# power.net
KiCad netlist of a schematic drawn in Altium Designer
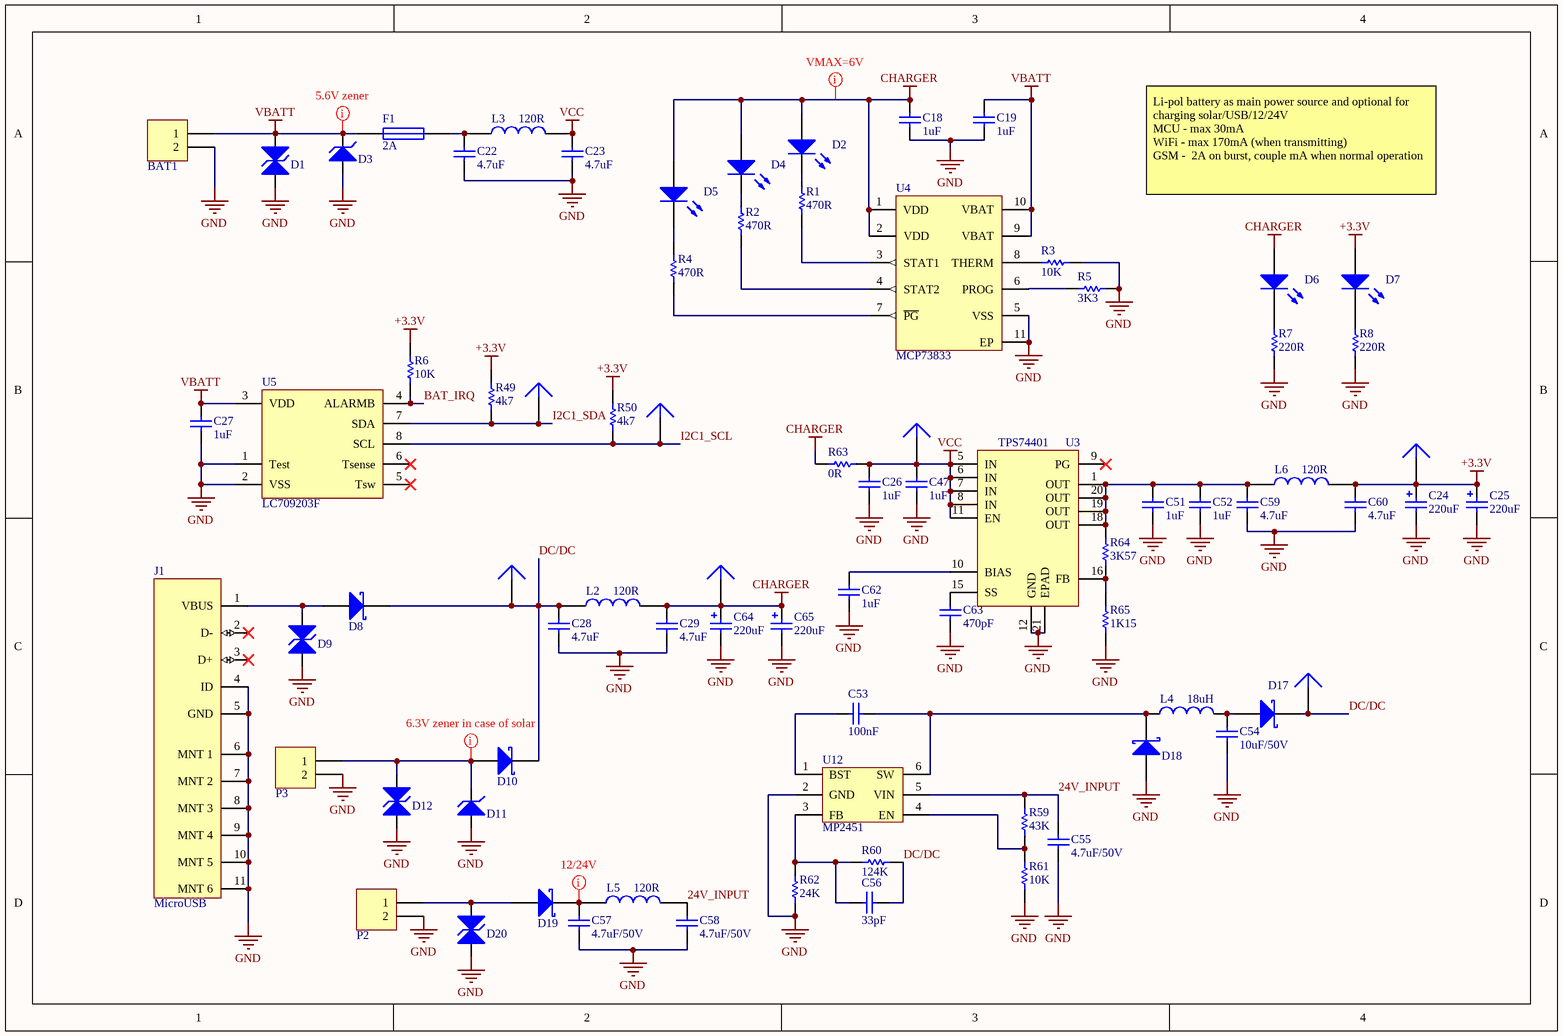
[diagram p0: power.SchDoc]

(export (version "E")
  (design (tool "Eeschema 10.0.6"))
  (components
    (comp (ref "BAT1")
      (value "Header 2")
      (footprint "HDR1X2")
      (description "Header, 2-Pin")
      (fields (field (name "PUBLISHER") "Altium Limited"))
      (libsource (lib "integratedLib") (part "Header 2"))
    )
    (comp (ref "C18")
      (value "1uF")
      (footprint "C0402")
      (description "Capacitor")
      (fields (field (name "Comment") "Cap 1uF"))
      (libsource (lib "integratedLib") (part "Cap 1uF"))
    )
    (comp (ref "C19")
      (value "1uF")
      (footprint "C0402")
      (description "Capacitor")
      (fields (field (name "Comment") "Cap 1uF"))
      (libsource (lib "integratedLib") (part "Cap 1uF"))
    )
    (comp (ref "C22")
      (value "4.7uF")
      (footprint "C0402")
      (description "Capacitor")
      (fields (field (name "Comment") "Cap 4.7uF"))
      (libsource (lib "integratedLib") (part "Cap 4.7uF"))
    )
    (comp (ref "C23")
      (value "4.7uF")
      (footprint "C0402")
      (description "Capacitor")
      (fields (field (name "Comment") "Cap 4.7uF"))
      (libsource (lib "integratedLib") (part "Cap 4.7uF"))
    )
    (comp (ref "C24")
      (value "220uF")
      (footprint "CAP-D")
      (description "Polarized Tantalum Capacitor")
      (fields (field (name "Comment") "Tantalum 220uF"))
      (libsource (lib "integratedLib") (part "Tantalum 220uF"))
    )
    (comp (ref "C25")
      (value "220uF")
      (footprint "CAP-D")
      (description "Polarized Tantalum Capacitor")
      (fields (field (name "Comment") "Tantalum 220uF"))
      (libsource (lib "integratedLib") (part "Tantalum 220uF"))
    )
    (comp (ref "C26")
      (value "1uF")
      (footprint "C0402")
      (description "Capacitor")
      (fields (field (name "Comment") "Cap 1uF"))
      (libsource (lib "integratedLib") (part "Cap 1uF"))
    )
    (comp (ref "C27")
      (value "1uF")
      (footprint "C0402")
      (description "Capacitor")
      (fields (field (name "Comment") "Cap 1uF"))
      (libsource (lib "integratedLib") (part "Cap 1uF"))
    )
    (comp (ref "C28")
      (value "4.7uF")
      (footprint "C0402")
      (description "Capacitor")
      (fields (field (name "Comment") "Cap 4.7uF"))
      (libsource (lib "integratedLib") (part "Cap 4.7uF"))
    )
    (comp (ref "C29")
      (value "4.7uF")
      (footprint "C0402")
      (description "Capacitor")
      (fields (field (name "Comment") "Cap 4.7uF"))
      (libsource (lib "integratedLib") (part "Cap 4.7uF"))
    )
    (comp (ref "C47")
      (value "1uF")
      (footprint "C0402")
      (description "Capacitor")
      (fields (field (name "Comment") "Cap 1uF"))
      (libsource (lib "integratedLib") (part "Cap 1uF"))
    )
    (comp (ref "C51")
      (value "1uF")
      (footprint "C0402")
      (description "Capacitor")
      (fields (field (name "Comment") "Cap 1uF"))
      (libsource (lib "integratedLib") (part "Cap 1uF"))
    )
    (comp (ref "C52")
      (value "1uF")
      (footprint "C0402")
      (description "Capacitor")
      (fields (field (name "Comment") "Cap 1uF"))
      (libsource (lib "integratedLib") (part "Cap 1uF"))
    )
    (comp (ref "C53")
      (value "100nF")
      (footprint "C0402")
      (description "Capacitor")
      (fields (field (name "Comment") "Cap 100nF"))
      (libsource (lib "integratedLib") (part "Cap 100nF"))
    )
    (comp (ref "C54")
      (value "10uF/50V")
      (footprint "C1206")
      (description "Capacitor")
      (fields (field (name "Comment") "Cap 10uF/50V"))
      (libsource (lib "integratedLib") (part "Cap 10uF/50V"))
    )
    (comp (ref "C55")
      (value "4.7uF/50V")
      (footprint "C1206")
      (description "Capacitor")
      (fields (field (name "Comment") "Cap 4.7uF/50V"))
      (libsource (lib "integratedLib") (part "Cap 4.7uF/50V"))
    )
    (comp (ref "C56")
      (value "33pF")
      (footprint "C0402")
      (description "Capacitor")
      (fields (field (name "Comment") "Cap 33pF"))
      (libsource (lib "integratedLib") (part "Cap 33pF"))
    )
    (comp (ref "C57")
      (value "4.7uF/50V")
      (footprint "C1206")
      (description "Capacitor")
      (fields (field (name "Comment") "Cap 4.7uF/50V"))
      (libsource (lib "integratedLib") (part "Cap 4.7uF/50V"))
    )
    (comp (ref "C58")
      (value "4.7uF/50V")
      (footprint "C1206")
      (description "Capacitor")
      (fields (field (name "Comment") "Cap 4.7uF/50V"))
      (libsource (lib "integratedLib") (part "Cap 4.7uF/50V"))
    )
    (comp (ref "C59")
      (value "4.7uF")
      (footprint "C0402")
      (description "Capacitor")
      (fields (field (name "Comment") "Cap 4.7uF"))
      (libsource (lib "integratedLib") (part "Cap 4.7uF"))
    )
    (comp (ref "C60")
      (value "4.7uF")
      (footprint "C0402")
      (description "Capacitor")
      (fields (field (name "Comment") "Cap 4.7uF"))
      (libsource (lib "integratedLib") (part "Cap 4.7uF"))
    )
    (comp (ref "C62")
      (value "1uF")
      (footprint "C0402")
      (description "Capacitor")
      (fields (field (name "Comment") "Cap 1uF"))
      (libsource (lib "integratedLib") (part "Cap 1uF"))
    )
    (comp (ref "C63")
      (value "470pF")
      (footprint "C0402")
      (description "Capacitor")
      (fields (field (name "Comment") "Cap 470pF"))
      (libsource (lib "integratedLib") (part "Cap 470pF"))
    )
    (comp (ref "C64")
      (value "220uF")
      (footprint "CAP-D")
      (description "Polarized Tantalum Capacitor")
      (fields (field (name "Comment") "Tantalum 220uF"))
      (libsource (lib "integratedLib") (part "Tantalum 220uF"))
    )
    (comp (ref "C65")
      (value "220uF")
      (footprint "CAP-D")
      (description "Polarized Tantalum Capacitor")
      (fields (field (name "Comment") "Tantalum 220uF"))
      (libsource (lib "integratedLib") (part "Tantalum 220uF"))
    )
    (comp (ref "D1")
      (value "TVS Bidirectional")
      (footprint "SMA")
      (description "SMAJ40CA")
      (fields (field (name "PUBLISHER") "Altium Limited"))
      (libsource (lib "integratedLib") (part "TVS_bidirectional"))
    )
    (comp (ref "D2")
      (value "LED")
      (footprint "0603LedRed")
      (description "Typical RED GaAs LED")
      (fields (field (name "PUBLISHER") "Altium Limited"))
      (libsource (lib "integratedLib") (part "LED"))
    )
    (comp (ref "D3")
      (value "Zener Diode")
      (footprint "miniMELF")
      (fields (field (name "PUBLISHER") "Altium Limited"))
      (libsource (lib "integratedLib") (part "Diode Zener"))
    )
    (comp (ref "D4")
      (value "LED")
      (footprint "0603LedRed")
      (description "Typical RED GaAs LED")
      (fields (field (name "PUBLISHER") "Altium Limited"))
      (libsource (lib "integratedLib") (part "LED"))
    )
    (comp (ref "D5")
      (value "LED")
      (footprint "0603LedRed")
      (description "Typical RED GaAs LED")
      (fields (field (name "PUBLISHER") "Altium Limited"))
      (libsource (lib "integratedLib") (part "LED"))
    )
    (comp (ref "D6")
      (value "LED")
      (footprint "0603LedRed")
      (description "Typical RED GaAs LED")
      (fields (field (name "PUBLISHER") "Altium Limited"))
      (libsource (lib "integratedLib") (part "LED"))
    )
    (comp (ref "D7")
      (value "LED")
      (footprint "0603LedRed")
      (description "Typical RED GaAs LED")
      (fields (field (name "PUBLISHER") "Altium Limited"))
      (libsource (lib "integratedLib") (part "LED"))
    )
    (comp (ref "D8")
      (value "STPS1L30U")
      (footprint "SOD-123A")
      (description "Schottky Rectifier")
      (fields (field (name "PUBLISHER") "Altium Limited"))
      (libsource (lib "integratedLib") (part "Diode Schottky"))
    )
    (comp (ref "D9")
      (value "TVS Bidirectional")
      (footprint "SMA")
      (description "SMAJ40CA")
      (fields (field (name "PUBLISHER") "Altium Limited"))
      (libsource (lib "integratedLib") (part "TVS_bidirectional"))
    )
    (comp (ref "D10")
      (value "STPS1L30U")
      (footprint "SOD-123A")
      (description "Schottky Rectifier")
      (fields (field (name "PUBLISHER") "Altium Limited"))
      (libsource (lib "integratedLib") (part "Diode Schottky"))
    )
    (comp (ref "D11")
      (value "Zener Diode")
      (footprint "miniMELF")
      (fields (field (name "PUBLISHER") "Altium Limited"))
      (libsource (lib "integratedLib") (part "Diode Zener"))
    )
    (comp (ref "D12")
      (value "TVS Bidirectional")
      (footprint "SMA")
      (description "SMAJ40CA")
      (fields (field (name "PUBLISHER") "Altium Limited"))
      (libsource (lib "integratedLib") (part "TVS_bidirectional"))
    )
    (comp (ref "D17")
      (value "D Schottky")
      (footprint "SOD-123A")
      (description "Schottky Diode")
      (fields (field (name "PUBLISHER") "Altium Limited"))
      (libsource (lib "supla_library") (part "D Schottky"))
    )
    (comp (ref "D18")
      (value "STPS1L30U")
      (footprint "SOD-123A")
      (description "Schottky Rectifier")
      (fields (field (name "PUBLISHER") "Altium Limited"))
      (libsource (lib "integratedLib") (part "Diode Schottky"))
    )
    (comp (ref "D19")
      (value "STPS1L30U")
      (footprint "SOD-123A")
      (description "Schottky Rectifier")
      (fields (field (name "PUBLISHER") "Altium Limited"))
      (libsource (lib "integratedLib") (part "Diode Schottky"))
    )
    (comp (ref "D20")
      (value "TVS Bidirectional")
      (footprint "SMA")
      (description "SMAJ40CA")
      (fields (field (name "PUBLISHER") "Altium Limited"))
      (libsource (lib "integratedLib") (part "TVS_bidirectional"))
    )
    (comp (ref "F1")
      (value "2A")
      (footprint "R1206")
      (description "Fuse\r\n2850030")
      (fields (field (name "PUBLISHER") "Altium Limited"))
      (libsource (lib "integratedLib") (part "Fuse_2A"))
    )
    (comp (ref "J1")
      (value "MicroUSB")
      (footprint "MicroUSB")
      (libsource (lib "integratedLib") (part "MicroUSB"))
    )
    (comp (ref "L2")
      (value "120R")
      (footprint "0805FerriteBead")
      (description "Ferrite bead")
      (fields (field (name "PUBLISHER") "Altium Limited"))
      (libsource (lib "integratedLib") (part "Ferrite bead 120R"))
    )
    (comp (ref "L3")
      (value "120R")
      (footprint "0805FerriteBead")
      (description "Ferrite bead")
      (fields (field (name "PUBLISHER") "Altium Limited"))
      (libsource (lib "integratedLib") (part "Ferrite bead 120R"))
    )
    (comp (ref "L4")
      (value "18uH")
      (footprint "WE-TPC_4828")
      (description "WE 744 043 180")
      (fields (field (name "Comment") "Inductor 18uH") (field (name "PUBLISHER") "Altium Limited"))
      (libsource (lib "integratedLib") (part "Inductor 18uH"))
    )
    (comp (ref "L5")
      (value "120R")
      (footprint "0805FerriteBead")
      (description "Ferrite bead")
      (fields (field (name "PUBLISHER") "Altium Limited"))
      (libsource (lib "integratedLib") (part "Ferrite bead 120R"))
    )
    (comp (ref "L6")
      (value "120R")
      (footprint "0805FerriteBead")
      (description "Ferrite bead")
      (fields (field (name "PUBLISHER") "Altium Limited"))
      (libsource (lib "integratedLib") (part "Ferrite bead 120R"))
    )
    (comp (ref "P2")
      (value "Header 2")
      (footprint "HDR1x2_screw")
      (description "Header, 2-Pin")
      (fields (field (name "PUBLISHER") "Altium Limited"))
      (libsource (lib "integratedLib") (part "Header 2"))
    )
    (comp (ref "P3")
      (value "Header 2")
      (footprint "HDR1x2_screw")
      (description "Header, 2-Pin")
      (fields (field (name "PUBLISHER") "Altium Limited"))
      (libsource (lib "integratedLib") (part "Header 2"))
    )
    (comp (ref "P12")
      (value "Plug")
      (footprint "pin smd")
      (fields (field (name "PUBLISHER") "Altium Limited"))
      (libsource (lib "integratedLib") (part "Plug"))
    )
    (comp (ref "P13")
      (value "Plug")
      (footprint "pin smd")
      (fields (field (name "PUBLISHER") "Altium Limited"))
      (libsource (lib "integratedLib") (part "Plug"))
    )
    (comp (ref "P15")
      (value "Plug")
      (footprint "pin smd")
      (fields (field (name "PUBLISHER") "Altium Limited"))
      (libsource (lib "integratedLib") (part "Plug"))
    )
    (comp (ref "P16")
      (value "Plug")
      (footprint "pin smd")
      (fields (field (name "PUBLISHER") "Altium Limited"))
      (libsource (lib "integratedLib") (part "Plug"))
    )
    (comp (ref "P17")
      (value "Plug")
      (footprint "pin smd")
      (fields (field (name "PUBLISHER") "Altium Limited"))
      (libsource (lib "integratedLib") (part "Plug"))
    )
    (comp (ref "P18")
      (value "Plug")
      (footprint "pin smd")
      (fields (field (name "PUBLISHER") "Altium Limited"))
      (libsource (lib "integratedLib") (part "Plug"))
    )
    (comp (ref "P19")
      (value "Plug")
      (footprint "pin smd")
      (fields (field (name "PUBLISHER") "Altium Limited"))
      (libsource (lib "integratedLib") (part "Plug"))
    )
    (comp (ref "R1")
      (value "470R")
      (footprint "R0402")
      (description "Resistor")
      (fields (field (name "Comment") "Res_470R"))
      (libsource (lib "integratedLib") (part "Res_470R"))
    )
    (comp (ref "R2")
      (value "470R")
      (footprint "R0402")
      (description "Resistor")
      (fields (field (name "Comment") "Res_470R"))
      (libsource (lib "integratedLib") (part "Res_470R"))
    )
    (comp (ref "R3")
      (value "10K")
      (footprint "R0402")
      (description "Resistor")
      (fields (field (name "Comment") "Res_10K"))
      (libsource (lib "integratedLib") (part "Res_10K"))
    )
    (comp (ref "R4")
      (value "470R")
      (footprint "R0402")
      (description "Resistor")
      (fields (field (name "Comment") "Res_470R"))
      (libsource (lib "integratedLib") (part "Res_470R"))
    )
    (comp (ref "R5")
      (value "3K3")
      (footprint "R0402")
      (description "Resistor")
      (fields (field (name "Comment") "Res_3K3"))
      (libsource (lib "integratedLib") (part "Res_3K3"))
    )
    (comp (ref "R6")
      (value "10K")
      (footprint "R0402")
      (description "Resistor")
      (fields (field (name "Comment") "Res_10K"))
      (libsource (lib "integratedLib") (part "Res_10K"))
    )
    (comp (ref "R7")
      (value "220R")
      (footprint "R0402")
      (description "Resistor")
      (fields (field (name "Comment") "Res_220R"))
      (libsource (lib "integratedLib") (part "Res_220R"))
    )
    (comp (ref "R8")
      (value "220R")
      (footprint "R0402")
      (description "Resistor")
      (fields (field (name "Comment") "Res_220R"))
      (libsource (lib "integratedLib") (part "Res_220R"))
    )
    (comp (ref "R49")
      (value "4k7")
      (footprint "R0402")
      (description "Resistor")
      (fields (field (name "Comment") "Res_4k7"))
      (libsource (lib "integratedLib") (part "Res_4k7"))
    )
    (comp (ref "R50")
      (value "4k7")
      (footprint "R0402")
      (description "Resistor")
      (fields (field (name "Comment") "Res_4k7"))
      (libsource (lib "integratedLib") (part "Res_4k7"))
    )
    (comp (ref "R59")
      (value "43K")
      (footprint "R0402")
      (description "Resistor")
      (fields (field (name "Comment") "Res_43K"))
      (libsource (lib "integratedLib") (part "Res_43K"))
    )
    (comp (ref "R60")
      (value "124K")
      (footprint "R0402")
      (description "Resistor")
      (fields (field (name "Comment") "Res_124K"))
      (libsource (lib "integratedLib") (part "Res_124K"))
    )
    (comp (ref "R61")
      (value "10K")
      (footprint "R0402")
      (description "Resistor")
      (fields (field (name "Comment") "Res_10K"))
      (libsource (lib "integratedLib") (part "Res_10K"))
    )
    (comp (ref "R62")
      (value "24K")
      (footprint "R0402")
      (description "Resistor")
      (fields (field (name "Comment") "Res_24K"))
      (libsource (lib "integratedLib") (part "Res_24K"))
    )
    (comp (ref "R63")
      (value "0R")
      (footprint "R0402")
      (description "Resistor")
      (fields (field (name "Comment") "Res_0R"))
      (libsource (lib "integratedLib") (part "Res_0R"))
    )
    (comp (ref "R64")
      (value "3K57")
      (footprint "R0402")
      (description "Resistor")
      (fields (field (name "Comment") "Res_3K57"))
      (libsource (lib "integratedLib") (part "Res_3K57"))
    )
    (comp (ref "R65")
      (value "1K15")
      (footprint "R0402")
      (description "Resistor")
      (fields (field (name "Comment") "Res_1K15"))
      (libsource (lib "integratedLib") (part "Res_1K15"))
    )
    (comp (ref "U3")
      (value "TPS74401")
      (footprint "PVQFN20")
      (description "Very Low Dropout Regulator")
      (libsource (lib "integratedLib") (part "TPS74401"))
    )
    (comp (ref "U4")
      (value "MCP73833")
      (footprint "DFN 3x3")
      (description "Li-Ion, Li-Polymer Charge Management Controller")
      (fields (field (name "PARTNUMBER") "MCP73831T-2ATI/OT"))
      (libsource (lib "integratedLib") (part "MCP73833"))
    )
    (comp (ref "U5")
      (value "LC709203F")
      (footprint "WDFN8")
      (description "Smart LiB GaugeBattery Fuel Gauge LSI For 1‐Cell Lithium‐ion/Polymer (Li+)")
      (libsource (lib "integratedLib") (part "LC709203F"))
    )
    (comp (ref "U12")
      (value "MP2451")
      (footprint "SOT23-6")
      (description "step down coverter")
      (libsource (lib "integratedLib") (part "MP2451"))
    )
  )
  (nets
    (net (code "1") (name "+3.3V") (class "Default")
      (node (ref "C24") (pin "2") (pinfunction "2_2") (pintype "passive"))
      (node (ref "C25") (pin "2") (pinfunction "2_2") (pintype "passive"))
      (node (ref "C60") (pin "2") (pinfunction "2_2") (pintype "passive"))
      (node (ref "D7") (pin "1") (pinfunction "A_1") (pintype "passive"))
      (node (ref "L6") (pin "2") (pinfunction "2_2") (pintype "passive"))
      (node (ref "P16") (pin "1") (pinfunction "1_1") (pintype "passive"))
      (node (ref "R49") (pin "2") (pinfunction "2_2") (pintype "passive"))
      (node (ref "R50") (pin "2") (pinfunction "2_2") (pintype "passive"))
      (node (ref "R6") (pin "2") (pinfunction "2_2") (pintype "passive"))
    )
    (net (code "2") (name "/24V_INPUT") (class "Default")
      (node (ref "C55") (pin "2") (pinfunction "2_2") (pintype "passive"))
      (node (ref "C58") (pin "2") (pinfunction "2_2") (pintype "passive"))
      (node (ref "L5") (pin "2") (pinfunction "2_2") (pintype "passive"))
      (node (ref "R59") (pin "2") (pinfunction "2_2") (pintype "passive"))
      (node (ref "U12") (pin "5") (pinfunction "VIN_5") (pintype "passive"))
    )
    (net (code "3") (name "/BAT_IRQ") (class "Default")
      (node (ref "R6") (pin "1") (pinfunction "1_1") (pintype "passive"))
      (node (ref "U5") (pin "4") (pinfunction "ALARMB_4") (pintype "passive"))
    )
    (net (code "4") (name "/DC{slash}DC") (class "Default")
      (node (ref "C28") (pin "2") (pinfunction "2_2") (pintype "passive"))
      (node (ref "C56") (pin "2") (pinfunction "2_2") (pintype "passive"))
      (node (ref "D10") (pin "2") (pinfunction "K_2") (pintype "passive"))
      (node (ref "D17") (pin "2") (pinfunction "K_2") (pintype "passive"))
      (node (ref "D8") (pin "2") (pinfunction "K_2") (pintype "passive"))
      (node (ref "L2") (pin "1") (pinfunction "1_1") (pintype "passive"))
      (node (ref "P17") (pin "1") (pinfunction "1_1") (pintype "passive"))
      (node (ref "P19") (pin "1") (pinfunction "1_1") (pintype "passive"))
      (node (ref "R60") (pin "2") (pinfunction "2_2") (pintype "passive"))
    )
    (net (code "5") (name "/I2C1_SCL") (class "Default")
      (node (ref "P13") (pin "1") (pinfunction "1_1") (pintype "passive"))
      (node (ref "R50") (pin "1") (pinfunction "1_1") (pintype "passive"))
      (node (ref "U5") (pin "8") (pinfunction "SCL_8") (pintype "passive"))
    )
    (net (code "6") (name "/I2C1_SDA") (class "Default")
      (node (ref "P12") (pin "1") (pinfunction "1_1") (pintype "passive"))
      (node (ref "R49") (pin "1") (pinfunction "1_1") (pintype "passive"))
      (node (ref "U5") (pin "7") (pinfunction "SDA_7") (pintype "passive"))
    )
    (net (code "7") (name "CHARGER") (class "Default")
      (node (ref "C18") (pin "2") (pinfunction "2_2") (pintype "passive"))
      (node (ref "C29") (pin "2") (pinfunction "2_2") (pintype "passive"))
      (node (ref "C64") (pin "2") (pinfunction "2_2") (pintype "passive"))
      (node (ref "C65") (pin "2") (pinfunction "2_2") (pintype "passive"))
      (node (ref "D2") (pin "1") (pinfunction "A_1") (pintype "passive"))
      (node (ref "D4") (pin "1") (pinfunction "A_1") (pintype "passive"))
      (node (ref "D5") (pin "1") (pinfunction "A_1") (pintype "passive"))
      (node (ref "D6") (pin "1") (pinfunction "A_1") (pintype "passive"))
      (node (ref "L2") (pin "2") (pinfunction "2_2") (pintype "passive"))
      (node (ref "P18") (pin "1") (pinfunction "1_1") (pintype "passive"))
      (node (ref "R63") (pin "1") (pinfunction "1_1") (pintype "passive"))
      (node (ref "U4") (pin "1") (pinfunction "VDD_1") (pintype "power_in"))
      (node (ref "U4") (pin "2") (pinfunction "VDD_2") (pintype "power_in"))
    )
    (net (code "8") (name "GND") (class "Default")
      (node (ref "BAT1") (pin "2") (pinfunction "2_2") (pintype "passive"))
      (node (ref "C18") (pin "1") (pinfunction "1_1") (pintype "passive"))
      (node (ref "C19") (pin "1") (pinfunction "1_1") (pintype "passive"))
      (node (ref "C22") (pin "1") (pinfunction "1_1") (pintype "passive"))
      (node (ref "C23") (pin "1") (pinfunction "1_1") (pintype "passive"))
      (node (ref "C24") (pin "1") (pinfunction "1_1") (pintype "passive"))
      (node (ref "C25") (pin "1") (pinfunction "1_1") (pintype "passive"))
      (node (ref "C26") (pin "1") (pinfunction "1_1") (pintype "passive"))
      (node (ref "C27") (pin "1") (pinfunction "1_1") (pintype "passive"))
      (node (ref "C28") (pin "1") (pinfunction "1_1") (pintype "passive"))
      (node (ref "C29") (pin "1") (pinfunction "1_1") (pintype "passive"))
      (node (ref "C47") (pin "1") (pinfunction "1_1") (pintype "passive"))
      (node (ref "C51") (pin "1") (pinfunction "1_1") (pintype "passive"))
      (node (ref "C52") (pin "1") (pinfunction "1_1") (pintype "passive"))
      (node (ref "C54") (pin "1") (pinfunction "1_1") (pintype "passive"))
      (node (ref "C55") (pin "1") (pinfunction "1_1") (pintype "passive"))
      (node (ref "C57") (pin "1") (pinfunction "1_1") (pintype "passive"))
      (node (ref "C58") (pin "1") (pinfunction "1_1") (pintype "passive"))
      (node (ref "C59") (pin "1") (pinfunction "1_1") (pintype "passive"))
      (node (ref "C60") (pin "1") (pinfunction "1_1") (pintype "passive"))
      (node (ref "C62") (pin "1") (pinfunction "1_1") (pintype "passive"))
      (node (ref "C63") (pin "1") (pinfunction "1_1") (pintype "passive"))
      (node (ref "C64") (pin "1") (pinfunction "1_1") (pintype "passive"))
      (node (ref "C65") (pin "1") (pinfunction "1_1") (pintype "passive"))
      (node (ref "D1") (pin "1") (pintype "passive"))
      (node (ref "D11") (pin "1") (pinfunction "A_1") (pintype "passive"))
      (node (ref "D12") (pin "1") (pintype "passive"))
      (node (ref "D18") (pin "1") (pinfunction "A_1") (pintype "passive"))
      (node (ref "D20") (pin "1") (pintype "passive"))
      (node (ref "D3") (pin "1") (pinfunction "A_1") (pintype "passive"))
      (node (ref "D9") (pin "1") (pintype "passive"))
      (node (ref "J1") (pin "10") (pinfunction "MNT_5_10") (pintype "passive"))
      (node (ref "J1") (pin "11") (pinfunction "MNT_6_11") (pintype "passive"))
      (node (ref "J1") (pin "4") (pinfunction "ID_4") (pintype "passive"))
      (node (ref "J1") (pin "5") (pinfunction "GND_5") (pintype "power_in"))
      (node (ref "J1") (pin "6") (pinfunction "MNT_1_6") (pintype "passive"))
      (node (ref "J1") (pin "7") (pinfunction "MNT_2_7") (pintype "passive"))
      (node (ref "J1") (pin "8") (pinfunction "MNT_3_8") (pintype "passive"))
      (node (ref "J1") (pin "9") (pinfunction "MNT_4_9") (pintype "passive"))
      (node (ref "P2") (pin "2") (pinfunction "2_2") (pintype "passive"))
      (node (ref "P3") (pin "2") (pinfunction "2_2") (pintype "passive"))
      (node (ref "R3") (pin "2") (pinfunction "2_2") (pintype "passive"))
      (node (ref "R5") (pin "2") (pinfunction "2_2") (pintype "passive"))
      (node (ref "R61") (pin "1") (pinfunction "1_1") (pintype "passive"))
      (node (ref "R62") (pin "1") (pinfunction "1_1") (pintype "passive"))
      (node (ref "R65") (pin "1") (pinfunction "1_1") (pintype "passive"))
      (node (ref "R7") (pin "1") (pinfunction "1_1") (pintype "passive"))
      (node (ref "R8") (pin "1") (pinfunction "1_1") (pintype "passive"))
      (node (ref "U12") (pin "2") (pinfunction "GND_2") (pintype "passive"))
      (node (ref "U3") (pin "12") (pinfunction "GND_12") (pintype "passive"))
      (node (ref "U3") (pin "21") (pinfunction "EPAD_21") (pintype "passive"))
      (node (ref "U4") (pin "11") (pinfunction "EP_11") (pintype "passive"))
      (node (ref "U4") (pin "5") (pinfunction "VSS_5") (pintype "passive"))
      (node (ref "U5") (pin "1") (pinfunction "Test_1") (pintype "power_in"))
      (node (ref "U5") (pin "2") (pinfunction "VSS_2") (pintype "power_in"))
    )
    (net (code "9") (name "Net-(C22-Pad2)") (class "Default")
      (node (ref "C22") (pin "2") (pinfunction "2_2") (pintype "passive"))
      (node (ref "F1") (pin "2") (pinfunction "2_2") (pintype "passive"))
      (node (ref "L3") (pin "1") (pinfunction "1_1") (pintype "passive"))
    )
    (net (code "10") (name "Net-(C51-Pad2)") (class "Default")
      (node (ref "C51") (pin "2") (pinfunction "2_2") (pintype "passive"))
      (node (ref "C52") (pin "2") (pinfunction "2_2") (pintype "passive"))
      (node (ref "C59") (pin "2") (pinfunction "2_2") (pintype "passive"))
      (node (ref "L6") (pin "1") (pinfunction "1_1") (pintype "passive"))
      (node (ref "R64") (pin "2") (pinfunction "2_2") (pintype "passive"))
      (node (ref "U3") (pin "1") (pinfunction "OUT_1") (pintype "passive"))
      (node (ref "U3") (pin "18") (pinfunction "OUT_18") (pintype "passive"))
      (node (ref "U3") (pin "19") (pinfunction "OUT_19") (pintype "passive"))
      (node (ref "U3") (pin "20") (pinfunction "OUT_20") (pintype "passive"))
    )
    (net (code "11") (name "Net-(D2-K)") (class "Default")
      (node (ref "D2") (pin "2") (pinfunction "K_2") (pintype "passive"))
      (node (ref "R1") (pin "2") (pinfunction "2_2") (pintype "passive"))
    )
    (net (code "12") (name "Net-(D4-K)") (class "Default")
      (node (ref "D4") (pin "2") (pinfunction "K_2") (pintype "passive"))
      (node (ref "R2") (pin "2") (pinfunction "2_2") (pintype "passive"))
    )
    (net (code "13") (name "Net-(D5-K)") (class "Default")
      (node (ref "D5") (pin "2") (pinfunction "K_2") (pintype "passive"))
      (node (ref "R4") (pin "2") (pinfunction "2_2") (pintype "passive"))
    )
    (net (code "14") (name "Net-(D6-K)") (class "Default")
      (node (ref "D6") (pin "2") (pinfunction "K_2") (pintype "passive"))
      (node (ref "R7") (pin "2") (pinfunction "2_2") (pintype "passive"))
    )
    (net (code "15") (name "Net-(D7-K)") (class "Default")
      (node (ref "D7") (pin "2") (pinfunction "K_2") (pintype "passive"))
      (node (ref "R8") (pin "2") (pinfunction "2_2") (pintype "passive"))
    )
    (net (code "16") (name "Net-(D8-A)") (class "Default")
      (node (ref "D8") (pin "1") (pinfunction "A_1") (pintype "passive"))
      (node (ref "D9") (pin "2") (pintype "passive"))
      (node (ref "J1") (pin "1") (pinfunction "VBUS_1") (pintype "power_in"))
    )
    (net (code "17") (name "Net-(D10-A)") (class "Default")
      (node (ref "D10") (pin "1") (pinfunction "A_1") (pintype "passive"))
      (node (ref "D11") (pin "2") (pinfunction "K_2") (pintype "passive"))
      (node (ref "D12") (pin "2") (pintype "passive"))
      (node (ref "P3") (pin "1") (pinfunction "1_1") (pintype "passive"))
    )
    (net (code "18") (name "Net-(D17-A)") (class "Default")
      (node (ref "C54") (pin "2") (pinfunction "2_2") (pintype "passive"))
      (node (ref "D17") (pin "1") (pinfunction "A_1") (pintype "passive"))
      (node (ref "L4") (pin "2") (pinfunction "2_2") (pintype "passive"))
    )
    (net (code "19") (name "Net-(D18-K)") (class "Default")
      (node (ref "C53") (pin "2") (pinfunction "2_2") (pintype "passive"))
      (node (ref "D18") (pin "2") (pinfunction "K_2") (pintype "passive"))
      (node (ref "L4") (pin "1") (pinfunction "1_1") (pintype "passive"))
      (node (ref "U12") (pin "6") (pinfunction "SW_6") (pintype "passive"))
    )
    (net (code "20") (name "Net-(D19-A)") (class "Default")
      (node (ref "D19") (pin "1") (pinfunction "A_1") (pintype "passive"))
      (node (ref "D20") (pin "2") (pintype "passive"))
      (node (ref "P2") (pin "1") (pinfunction "1_1") (pintype "passive"))
    )
    (net (code "21") (name "Net-(D19-K)") (class "Default")
      (node (ref "C57") (pin "2") (pinfunction "2_2") (pintype "passive"))
      (node (ref "D19") (pin "2") (pinfunction "K_2") (pintype "passive"))
      (node (ref "L5") (pin "1") (pinfunction "1_1") (pintype "passive"))
    )
    (net (code "22") (name "Net-(U3-BIAS)") (class "Default")
      (node (ref "C62") (pin "2") (pinfunction "2_2") (pintype "passive"))
      (node (ref "U3") (pin "10") (pinfunction "BIAS_10") (pintype "passive"))
    )
    (net (code "23") (name "Net-(U3-FB)") (class "Default")
      (node (ref "R64") (pin "1") (pinfunction "1_1") (pintype "passive"))
      (node (ref "R65") (pin "2") (pinfunction "2_2") (pintype "passive"))
      (node (ref "U3") (pin "16") (pinfunction "FB_16") (pintype "passive"))
    )
    (net (code "24") (name "Net-(U3-SS)") (class "Default")
      (node (ref "C63") (pin "2") (pinfunction "2_2") (pintype "passive"))
      (node (ref "U3") (pin "15") (pinfunction "SS_15") (pintype "passive"))
    )
    (net (code "25") (name "Net-(U4-PROG)") (class "Default")
      (node (ref "R5") (pin "1") (pinfunction "1_1") (pintype "passive"))
      (node (ref "U4") (pin "6") (pinfunction "PROG_6") (pintype "passive"))
    )
    (net (code "26") (name "Net-(U4-STAT1)") (class "Default")
      (node (ref "R1") (pin "1") (pinfunction "1_1") (pintype "passive"))
      (node (ref "U4") (pin "3") (pinfunction "STAT1_3") (pintype "output"))
    )
    (net (code "27") (name "Net-(U4-STAT2)") (class "Default")
      (node (ref "R2") (pin "1") (pinfunction "1_1") (pintype "passive"))
      (node (ref "U4") (pin "4") (pinfunction "STAT2_4") (pintype "output"))
    )
    (net (code "28") (name "Net-(U4-THERM)") (class "Default")
      (node (ref "R3") (pin "1") (pinfunction "1_1") (pintype "passive"))
      (node (ref "U4") (pin "8") (pinfunction "THERM_8") (pintype "passive"))
    )
    (net (code "29") (name "Net-(U4-~{PG})") (class "Default")
      (node (ref "R4") (pin "1") (pinfunction "1_1") (pintype "passive"))
      (node (ref "U4") (pin "7") (pinfunction "~{PG}_7") (pintype "output"))
    )
    (net (code "30") (name "Net-(U12-BST)") (class "Default")
      (node (ref "C53") (pin "1") (pinfunction "1_1") (pintype "passive"))
      (node (ref "U12") (pin "1") (pinfunction "BST_1") (pintype "passive"))
    )
    (net (code "31") (name "Net-(U12-EN)") (class "Default")
      (node (ref "R59") (pin "1") (pinfunction "1_1") (pintype "passive"))
      (node (ref "R61") (pin "2") (pinfunction "2_2") (pintype "passive"))
      (node (ref "U12") (pin "4") (pinfunction "EN_4") (pintype "passive"))
    )
    (net (code "32") (name "Net-(U12-FB)") (class "Default")
      (node (ref "C56") (pin "1") (pinfunction "1_1") (pintype "passive"))
      (node (ref "R60") (pin "1") (pinfunction "1_1") (pintype "passive"))
      (node (ref "R62") (pin "2") (pinfunction "2_2") (pintype "passive"))
      (node (ref "U12") (pin "3") (pinfunction "FB_3") (pintype "passive"))
    )
    (net (code "33") (name "VBATT") (class "Default")
      (node (ref "BAT1") (pin "1") (pinfunction "1_1") (pintype "passive"))
      (node (ref "C19") (pin "2") (pinfunction "2_2") (pintype "passive"))
      (node (ref "C27") (pin "2") (pinfunction "2_2") (pintype "passive"))
      (node (ref "D1") (pin "2") (pintype "passive"))
      (node (ref "D3") (pin "2") (pinfunction "K_2") (pintype "passive"))
      (node (ref "F1") (pin "1") (pinfunction "1_1") (pintype "passive"))
      (node (ref "U4") (pin "10") (pinfunction "VBAT_10") (pintype "power_in"))
      (node (ref "U4") (pin "9") (pinfunction "VBAT_9") (pintype "power_in"))
      (node (ref "U5") (pin "3") (pinfunction "VDD_3") (pintype "passive"))
    )
    (net (code "34") (name "VCC") (class "Default")
      (node (ref "C23") (pin "2") (pinfunction "2_2") (pintype "passive"))
      (node (ref "C26") (pin "2") (pinfunction "2_2") (pintype "passive"))
      (node (ref "C47") (pin "2") (pinfunction "2_2") (pintype "passive"))
      (node (ref "L3") (pin "2") (pinfunction "2_2") (pintype "passive"))
      (node (ref "P15") (pin "1") (pinfunction "1_1") (pintype "passive"))
      (node (ref "R63") (pin "2") (pinfunction "2_2") (pintype "passive"))
      (node (ref "U3") (pin "11") (pinfunction "EN_11") (pintype "passive"))
      (node (ref "U3") (pin "5") (pinfunction "IN_5") (pintype "passive"))
      (node (ref "U3") (pin "6") (pinfunction "IN_6") (pintype "passive"))
      (node (ref "U3") (pin "7") (pinfunction "IN_7") (pintype "passive"))
      (node (ref "U3") (pin "8") (pinfunction "IN_8") (pintype "passive"))
    )
    (net (code "35") (name "unconnected-(J1-D+-Pad3)") (class "Default")
      (node (ref "J1") (pin "3") (pinfunction "D+_3") (pintype "bidirectional+no_connect"))
    )
    (net (code "36") (name "unconnected-(J1-D--Pad2)") (class "Default")
      (node (ref "J1") (pin "2") (pinfunction "D-_2") (pintype "bidirectional+no_connect"))
    )
    (net (code "37") (name "unconnected-(U3-PG-Pad9)") (class "Default")
      (node (ref "U3") (pin "9") (pinfunction "PG_9") (pintype "passive+no_connect"))
    )
    (net (code "38") (name "unconnected-(U5-Tsense-Pad6)") (class "Default")
      (node (ref "U5") (pin "6") (pinfunction "Tsense_6") (pintype "power_in+no_connect"))
    )
    (net (code "39") (name "unconnected-(U5-Tsw-Pad5)") (class "Default")
      (node (ref "U5") (pin "5") (pinfunction "Tsw_5") (pintype "power_in+no_connect"))
    )
  )
)
